# Power.net
KiCad netlist of a schematic drawn in Altium Designer
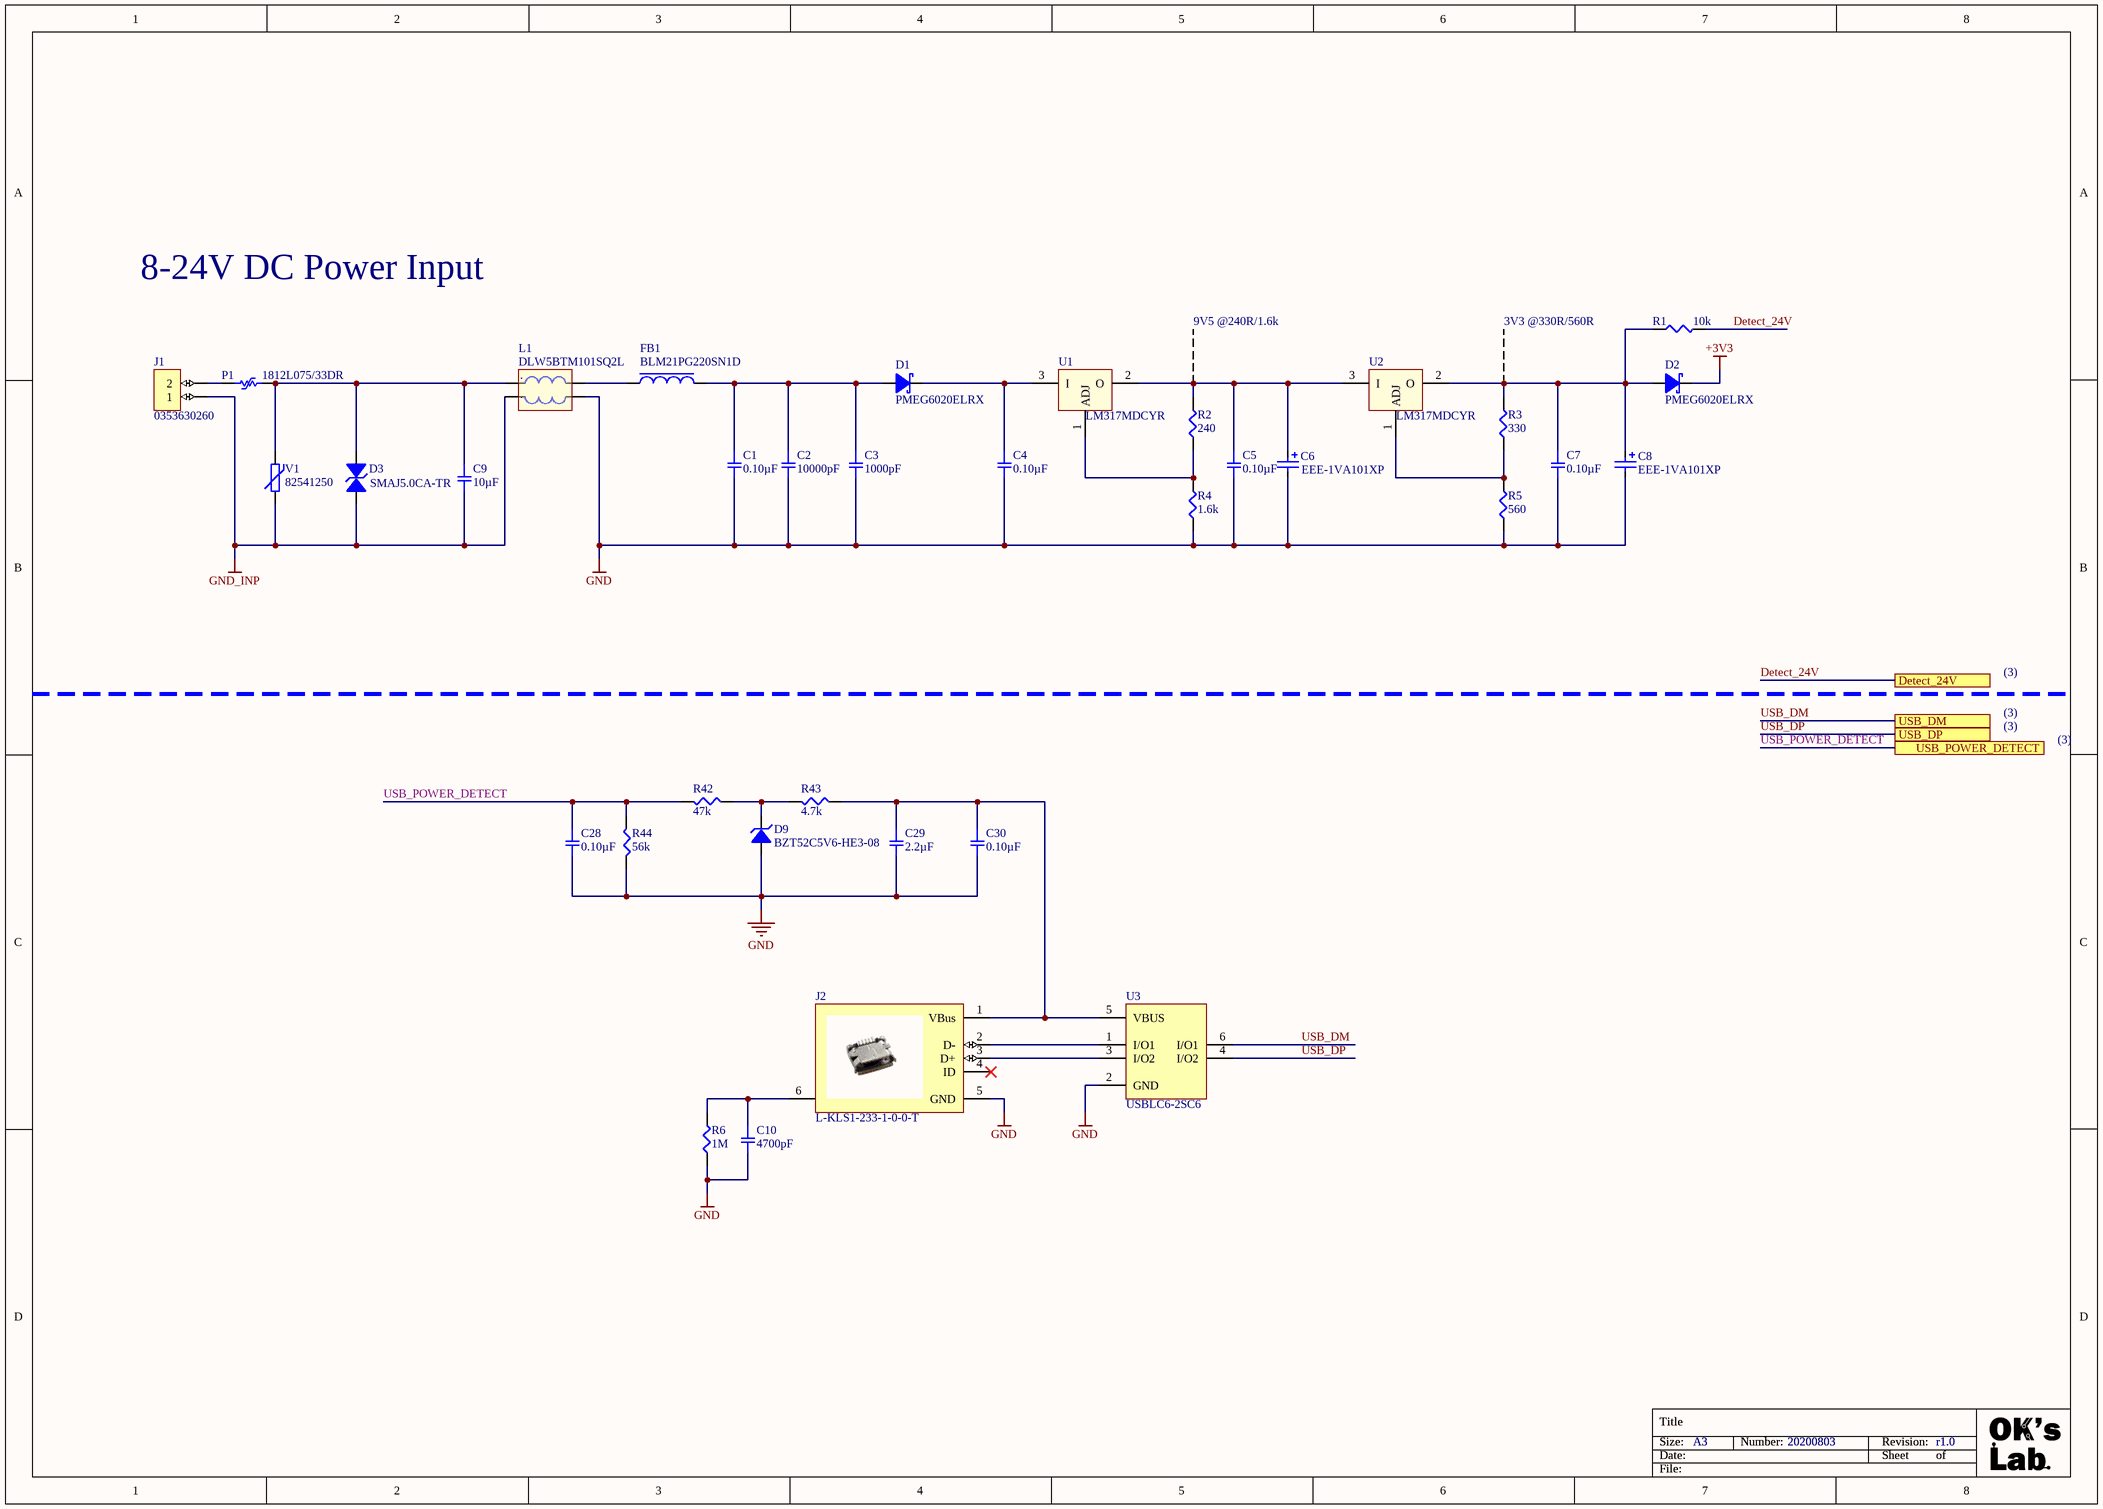
[diagram p0: Power.SchDoc]

(export (version "E")
  (design (tool "Eeschema 10.0.6"))
  (components
    (comp (ref "C1")
      (value "0.10µF")
      (footprint "SMD-0805C")
      (description "CAP CER 0.1UF 50V X7R 0805")
      (fields
        (field (name "DIGI-KEY PART NUMBER") "490-11955-1-ND")
        (field (name "PART NUMBER") "GCD21BR71H104KA01L")
      )
      (libsource (lib "capacitor_murata_0805") (part "GCD21BR71H104KA01L"))
    )
    (comp (ref "C2")
      (value "10000pF")
      (footprint "SMD-0805C")
      (description "CAP CER 10000PF 50V X7R 0805")
      (fields
        (field (name "DIGI-KEY PART NUMBER") "490-5841-1-ND")
        (field (name "PART NUMBER") "GCJ216R71H103KA01D")
      )
      (libsource (lib "capacitor_murata_0805") (part "GCJ216R71H103KA01D"))
    )
    (comp (ref "C3")
      (value "1000pF")
      (footprint "SMD-0805C")
      (description "CAP CER 1000PF 50V X7R 0805")
      (fields
        (field (name "DIGI-KEY PART NUMBER") "490-5813-1-ND")
        (field (name "PART NUMBER") "GCJ216R71H102KA01D")
      )
      (libsource (lib "capacitor_murata_0805") (part "GCJ216R71H102KA01D"))
    )
    (comp (ref "C4")
      (value "0.10µF")
      (footprint "SMD-0805C")
      (description "CAP CER 0.1UF 50V X7R 0805")
      (fields
        (field (name "DIGI-KEY PART NUMBER") "490-11955-1-ND")
        (field (name "PART NUMBER") "GCD21BR71H104KA01L")
      )
      (libsource (lib "capacitor_murata_0805") (part "GCD21BR71H104KA01L"))
    )
    (comp (ref "C5")
      (value "0.10µF")
      (footprint "SMD-0805C")
      (description "CAP CER 0.1UF 50V X7R 0805")
      (fields
        (field (name "DIGI-KEY PART NUMBER") "490-11955-1-ND")
        (field (name "PART NUMBER") "GCD21BR71H104KA01L")
      )
      (libsource (lib "capacitor_murata_0805") (part "GCD21BR71H104KA01L"))
    )
    (comp (ref "C6")
      (value "EEE-1VA101XP")
      (footprint "AE_C_R6")
      (description "CAP ALUM 100UF 20% 35V SMD")
      (fields
        (field (name "TOLERANCE") "±20%")
        (field (name "MANUFACTURER") "Panasonic Electronic Components")
      )
      (libsource (lib "Altium_Lib") (part "Capacitor_(Electrolytic)__EEE-1VA101XP"))
    )
    (comp (ref "C7")
      (value "0.10µF")
      (footprint "SMD-0805C")
      (description "CAP CER 0.1UF 50V X7R 0805")
      (fields
        (field (name "DIGI-KEY PART NUMBER") "490-11955-1-ND")
        (field (name "PART NUMBER") "GCD21BR71H104KA01L")
      )
      (libsource (lib "capacitor_murata_0805") (part "GCD21BR71H104KA01L"))
    )
    (comp (ref "C8")
      (value "EEE-1VA101XP")
      (footprint "AE_C_R6")
      (description "CAP ALUM 100UF 20% 35V SMD")
      (fields
        (field (name "TOLERANCE") "±20%")
        (field (name "MANUFACTURER") "Panasonic Electronic Components")
      )
      (libsource (lib "Altium_Lib") (part "Capacitor_(Electrolytic)__EEE-1VA101XP"))
    )
    (comp (ref "C9")
      (value "10µF")
      (footprint "SMD-1206C")
      (description "CAP CER 10UF 50V X5R 1206")
      (fields
        (field (name "DIGI-KEY PART NUMBER") "490-5961-1-ND")
        (field (name "PART NUMBER") "GRM31CR61H106KA12L")
      )
      (libsource (lib "capacitor_murata_1206") (part "GRM31CR61H106KA12L"))
    )
    (comp (ref "C10")
      (value "4700pF")
      (footprint "SMD-0805C")
      (description "CAP CER 4700PF 250V X7R 0805")
      (fields
        (field (name "DIGI-KEY PART NUMBER") "490-5593-1-ND")
        (field (name "PART NUMBER") "GCJ21AR72E472KXJ1D")
      )
      (libsource (lib "capacitor_murata_0805") (part "GCJ21AR72E472KXJ1D"))
    )
    (comp (ref "C28")
      (value "0.10µF")
      (footprint "SMD-0603C")
      (description "CAP CER 0.1UF 50V X7R 0603")
      (fields
        (field (name "DIGI-KEY PART NUMBER") "490-5798-1-ND")
        (field (name "MANUFACTURER") "Murata Electronics North America")
      )
      (libsource (lib "capacitor_murata_0603") (part "GCJ188R71H104KA12D"))
    )
    (comp (ref "C29")
      (value "2.2µF")
      (footprint "SMD-0603C")
      (description "CAP CER 2.2UF 16V X7S 0603")
      (fields
        (field (name "DIGI-KEY PART NUMBER") "490-12731-1-ND")
        (field (name "MANUFACTURER") "Murata Electronics North America")
      )
      (libsource (lib "capacitor_murata_0603") (part "GRM188C71C225KE11D"))
    )
    (comp (ref "C30")
      (value "0.10µF")
      (footprint "SMD-0603C")
      (description "CAP CER 0.1UF 50V X7R 0603")
      (fields
        (field (name "DIGI-KEY PART NUMBER") "490-5798-1-ND")
        (field (name "MANUFACTURER") "Murata Electronics North America")
      )
      (libsource (lib "capacitor_murata_0603") (part "GCJ188R71H104KA12D"))
    )
    (comp (ref "D1")
      (value "PMEG6020ELRX")
      (footprint "SOD123W")
      (description "DIODE SCHOTTKY 60V 2A CFP3")
      (fields (field (name "MANUFACTURER") "Nexperia"))
      (libsource (lib "Altium_Lib") (part "DIODE_PMEG6020ELRX"))
    )
    (comp (ref "D2")
      (value "PMEG6020ELRX")
      (footprint "SOD123W")
      (description "DIODE SCHOTTKY 60V 2A CFP3")
      (fields (field (name "MANUFACTURER") "Nexperia"))
      (libsource (lib "Altium_Lib") (part "DIODE_PMEG6020ELRX"))
    )
    (comp (ref "D3")
      (value "SMAJ5.0CA-TR")
      (footprint "DO-214AA-SMB -nonPOL")
      (description "TVS DIODE 26VWM 42.1VC SMB")
      (fields (field (name "MANUFACTURER") "STMicroelectronics") (field (name "BASE PART NUMBER") "SMAJ"))
      (libsource (lib "Altium_Lib") (part "DIODE_SMBJ26CA"))
    )
    (comp (ref "D9")
      (value "BZT52C5V6-HE3-08")
      (footprint "SOD123")
      (description "DIODE ZENER 5.6V 410MW SOD123")
      (fields (field (name "MANUFACTURER") "Vishay") (field (name "TOLERANCE") "5%"))
      (libsource (lib "Altium_Lib") (part "DIODE_BZT52C5V6-HE3-08"))
    )
    (comp (ref "FB1")
      (value "BLM21PG220SN1D")
      (footprint "L-0805")
      (description "FERRITE BEAD 22 OHM 0805 1LN")
      (fields (field (name "MANUFACTURER") "Murata") (field (name "TOLERANCE") "25%"))
      (libsource (lib "Altium_Lib") (part "Ferrite_Bead__BLM21PG220SN1D"))
    )
    (comp (ref "J1")
      (value "0353630260")
      (footprint "CONN_2_POS__0353630260")
      (description "CONN HEADER 2POS 2MM R/A TIN")
      (fields (field (name "MANUFACTURER") "Molex, LLC"))
      (libsource (lib "Altium_Lib") (part "CONN_2_POS__0353630260"))
    )
    (comp (ref "J2")
      (value "L-KLS1-233-1-0-0-T")
      (footprint "USB_MICRO_1981584-1")
      (description "Conn Micro USB 2.0 Type AB RCP 5 POS 0.65mm Solder RA SMD 5 Terminal 1 Port T/R")
      (fields (field (name "MANUFACTURER") "KLS Electronic"))
      (libsource (lib "Altium_Lib") (part "USB_Micro_L-KLS1-233-1-0-0-T"))
    )
    (comp (ref "L1")
      (value "DLW5BTM101SQ2L")
      (footprint "DLW5BTMxxxxxxx")
      (description "2 Line CommonModeChoke, SMD 6A")
      (libsource (lib "SinapstekLib") (part "DLW5BTM101SQ2L"))
    )
    (comp (ref "P1")
      (value "1812L075/33DR")
      (footprint "PTC-1812")
      (description "PTC RESET FUSE 33V 750MA 1812")
      (fields (field (name "MANUFACTURER") "Littelfuse Inc."))
      (libsource (lib "Altium_Lib") (part "PTC__1812L075/33DR"))
    )
    (comp (ref "R1")
      (value "10k")
      (footprint "SMD-0603-RES")
      (description "RES SMD 10K OHM 5% 1/10W 0603")
      (fields (field (name "PART NUMBER") "ERJ-3GEYJ103V") (field (name "DIGI-KEY PART NUMBER") "P10KGCT-ND"))
      (libsource (lib "Panasonic_ERJ_0603") (part "ERJ-3GEYJ103V"))
    )
    (comp (ref "R2")
      (value "240")
      (footprint "SMD-0603-RES")
      (description "RES SMD 240 OHM 1% 1/10W 0603")
      (fields (field (name "PART NUMBER") "ERJ-3EKF2400V") (field (name "DIGI-KEY PART NUMBER") "P240HCT-ND"))
      (libsource (lib "Panasonic_ERJ_0603") (part "ERJ-3EKF2400V"))
    )
    (comp (ref "R3")
      (value "330")
      (footprint "SMD-0603-RES")
      (description "RES SMD 330 OHM 1% 1/10W 0603")
      (fields (field (name "PART NUMBER") "ERJ-3EKF3300V") (field (name "DIGI-KEY PART NUMBER") "P330HCT-ND"))
      (libsource (lib "Panasonic_ERJ_0603") (part "ERJ-3EKF3300V"))
    )
    (comp (ref "R4")
      (value "1.6k")
      (footprint "SMD-0603-RES")
      (description "RES SMD 1.6K OHM 1% 1/10W 0603")
      (fields
        (field (name "PART NUMBER") "ERJ-3EKF1601V")
        (field (name "DIGI-KEY PART NUMBER") "P1.60KHCT-ND")
      )
      (libsource (lib "Panasonic_ERJ_0603") (part "ERJ-3EKF1601V"))
    )
    (comp (ref "R5")
      (value "560")
      (footprint "SMD-0603-RES")
      (description "RES SMD 560 OHM 1% 1/10W 0603")
      (fields (field (name "PART NUMBER") "ERJ-3EKF5600V") (field (name "DIGI-KEY PART NUMBER") "P560HCT-ND"))
      (libsource (lib "Panasonic_ERJ_0603") (part "ERJ-3EKF5600V"))
    )
    (comp (ref "R6")
      (value "1M")
      (footprint "SMD-0805-RES")
      (description "RES SMD 1M OHM 5% 1/8W 0805")
      (fields
        (field (name "PART NUMBER") "ERJ-6GEYJ105V")
        (field (name "DIGI-KEY PART NUMBER") "P1.0MACT-ND")
      )
      (libsource (lib "Panasonic_ERJ_0805") (part "ERJ-6GEYJ105V"))
    )
    (comp (ref "R42")
      (value "47k")
      (footprint "SMD-0603-RES")
      (description "RES SMD 47K OHM 1% 1/10W 0603")
      (fields
        (field (name "DIGI-KEY PART NUMBER") "P47.0KHCT-ND")
        (field (name "MANUFACTURER") "Panasonic Electronic Components")
      )
      (libsource (lib "Panasonic_ERJ_0603") (part "ERJ-3EKF4702V"))
    )
    (comp (ref "R43")
      (value "4.7k")
      (footprint "SMD-0603-RES")
      (description "RES SMD 4.7K OHM 1% 1/10W 0603")
      (fields
        (field (name "DIGI-KEY PART NUMBER") "P4.70KHCT-ND")
        (field (name "MANUFACTURER") "Panasonic Electronic Components")
      )
      (libsource (lib "Panasonic_ERJ_0603") (part "ERJ-3EKF4701V"))
    )
    (comp (ref "R44")
      (value "56k")
      (footprint "SMD-0603-RES")
      (description "RES SMD 56K OHM 1% 1/10W 0603")
      (fields
        (field (name "DIGI-KEY PART NUMBER") "P56.0KHCT-ND")
        (field (name "MANUFACTURER") "Panasonic Electronic Components")
      )
      (libsource (lib "Panasonic_ERJ_0603") (part "ERJ-3EKF5602V"))
    )
    (comp (ref "U1")
      (value "LM317MDCYR")
      (footprint "SOT-223-4")
      (description "IC REG LINEAR ADJ 0.5A SOT223")
      (fields (field (name "MANUFACTURER") "Texas Instruments"))
      (libsource (lib "Altium_Lib") (part "LM317MDCY"))
    )
    (comp (ref "U2")
      (value "LM317MDCYR")
      (footprint "SOT-223-4")
      (description "IC REG LINEAR ADJ 0.5A SOT223")
      (fields (field (name "MANUFACTURER") "Texas Instruments"))
      (libsource (lib "Altium_Lib") (part "LM317MDCY"))
    )
    (comp (ref "U3")
      (value "USBLC6-2SC6")
      (footprint "SOT23-6")
      (description "TVS DIODE 5.25V 17V SOT23-6")
      (fields (field (name "MANUFACTURER") "STMicroelectronics") (field (name "BASE PART NUMBER") "USBLC6-2"))
      (libsource (lib "Altium_Lib") (part "USBLC6-2SC6"))
    )
    (comp (ref "V1")
      (value "82541250")
      (footprint "V-1206")
      (description "VARISTOR 39V 200A 1206")
      (fields (field (name "MANUFACTURER") "Wurth Electronics Inc."))
      (libsource (lib "Altium_Lib") (part "VARISTOR_82541250"))
    )
  )
  (nets
    (net (code "1") (name "+3V3") (class "Default")
      (node (ref "D2") (pin "1") (pinfunction "K_1") (pintype "passive"))
    )
    (net (code "2") (name "/Detect_24V") (class "Default")
      (node (ref "R1") (pin "2") (pinfunction "2_2") (pintype "passive"))
    )
    (net (code "3") (name "/USB_DM") (class "Default")
      (node (ref "U3") (pin "6") (pinfunction "I/O1_6") (pintype "passive"))
    )
    (net (code "4") (name "/USB_DP") (class "Default")
      (node (ref "U3") (pin "4") (pinfunction "I/O2_4") (pintype "passive"))
    )
    (net (code "5") (name "/USB_POWER_DETECT") (class "Default")
      (node (ref "C28") (pin "1") (pinfunction "1_1") (pintype "passive"))
      (node (ref "R42") (pin "2") (pinfunction "2_2") (pintype "passive"))
      (node (ref "R44") (pin "2") (pinfunction "2_2") (pintype "passive"))
    )
    (net (code "6") (name "GND") (class "Default")
      (node (ref "C1") (pin "2") (pinfunction "2_2") (pintype "passive"))
      (node (ref "C10") (pin "2") (pinfunction "2_2") (pintype "passive"))
      (node (ref "C2") (pin "2") (pinfunction "2_2") (pintype "passive"))
      (node (ref "C28") (pin "2") (pinfunction "2_2") (pintype "passive"))
      (node (ref "C29") (pin "2") (pinfunction "2_2") (pintype "passive"))
      (node (ref "C3") (pin "2") (pinfunction "2_2") (pintype "passive"))
      (node (ref "C30") (pin "2") (pinfunction "2_2") (pintype "passive"))
      (node (ref "C4") (pin "2") (pinfunction "2_2") (pintype "passive"))
      (node (ref "C5") (pin "2") (pinfunction "2_2") (pintype "passive"))
      (node (ref "C6") (pin "2") (pinfunction "2_2") (pintype "passive"))
      (node (ref "C7") (pin "2") (pinfunction "2_2") (pintype "passive"))
      (node (ref "C8") (pin "2") (pinfunction "2_2") (pintype "passive"))
      (node (ref "D9") (pin "1") (pinfunction "T1_1") (pintype "passive"))
      (node (ref "J2") (pin "5") (pinfunction "GND_5") (pintype "passive"))
      (node (ref "L1") (pin "3") (pinfunction "B2_3") (pintype "passive"))
      (node (ref "R4") (pin "1") (pinfunction "1_1") (pintype "passive"))
      (node (ref "R44") (pin "1") (pinfunction "1_1") (pintype "passive"))
      (node (ref "R5") (pin "1") (pinfunction "1_1") (pintype "passive"))
      (node (ref "R6") (pin "1") (pinfunction "1_1") (pintype "passive"))
      (node (ref "U3") (pin "2") (pinfunction "GND_2") (pintype "passive"))
    )
    (net (code "7") (name "GND_INP") (class "Default")
      (node (ref "C9") (pin "2") (pinfunction "2_2") (pintype "passive"))
      (node (ref "D3") (pin "2") (pinfunction "T2_2") (pintype "passive"))
      (node (ref "J1") (pin "1") (pinfunction "1_1") (pintype "bidirectional"))
      (node (ref "L1") (pin "4") (pinfunction "B1_4") (pintype "passive"))
      (node (ref "V1") (pin "1") (pinfunction "1_1") (pintype "passive"))
    )
    (net (code "8") (name "Net-(D1-A)") (class "Default")
      (node (ref "C1") (pin "1") (pinfunction "1_1") (pintype "passive"))
      (node (ref "C2") (pin "1") (pinfunction "1_1") (pintype "passive"))
      (node (ref "C3") (pin "1") (pinfunction "1_1") (pintype "passive"))
      (node (ref "D1") (pin "2") (pinfunction "A_2") (pintype "passive"))
      (node (ref "FB1") (pin "2") (pinfunction "2_2") (pintype "passive"))
    )
    (net (code "9") (name "Net-(D1-K)") (class "Default")
      (node (ref "C4") (pin "1") (pinfunction "1_1") (pintype "passive"))
      (node (ref "D1") (pin "1") (pinfunction "K_1") (pintype "passive"))
      (node (ref "U1") (pin "3") (pinfunction "I_3") (pintype "power_in"))
    )
    (net (code "10") (name "Net-(D2-A)") (class "Default")
      (node (ref "C7") (pin "1") (pinfunction "1_1") (pintype "passive"))
      (node (ref "C8") (pin "1") (pinfunction "1_1") (pintype "passive"))
      (node (ref "D2") (pin "2") (pinfunction "A_2") (pintype "passive"))
      (node (ref "R1") (pin "1") (pinfunction "1_1") (pintype "passive"))
      (node (ref "R3") (pin "2") (pinfunction "2_2") (pintype "passive"))
      (node (ref "U2") (pin "2") (pinfunction "O_2") (pintype "power_in"))
    )
    (net (code "11") (name "Net-(D3-T1)") (class "Default")
      (node (ref "C9") (pin "1") (pinfunction "1_1") (pintype "passive"))
      (node (ref "D3") (pin "1") (pinfunction "T1_1") (pintype "passive"))
      (node (ref "L1") (pin "1") (pinfunction "A1_1") (pintype "passive"))
      (node (ref "P1") (pin "2") (pinfunction "2_2") (pintype "passive"))
      (node (ref "V1") (pin "2") (pinfunction "2_2") (pintype "passive"))
    )
    (net (code "12") (name "Net-(D9-T2)") (class "Default")
      (node (ref "D9") (pin "2") (pinfunction "T2_2") (pintype "passive"))
      (node (ref "R42") (pin "1") (pinfunction "1_1") (pintype "passive"))
      (node (ref "R43") (pin "2") (pinfunction "2_2") (pintype "passive"))
    )
    (net (code "13") (name "Net-(J1-Pad2)") (class "Default")
      (node (ref "J1") (pin "2") (pinfunction "2_2") (pintype "bidirectional"))
      (node (ref "P1") (pin "1") (pinfunction "1_1") (pintype "passive"))
    )
    (net (code "14") (name "Net-(J2-D+)") (class "Default")
      (node (ref "J2") (pin "3") (pinfunction "D+_3") (pintype "bidirectional"))
      (node (ref "U3") (pin "3") (pinfunction "I/O2_3") (pintype "passive"))
    )
    (net (code "15") (name "Net-(J2-D-)") (class "Default")
      (node (ref "J2") (pin "2") (pinfunction "D-_2") (pintype "bidirectional"))
      (node (ref "U3") (pin "1") (pinfunction "I/O1_1") (pintype "passive"))
    )
    (net (code "16") (name "Net-(J2-Shield)") (class "Default")
      (node (ref "C10") (pin "1") (pinfunction "1_1") (pintype "passive"))
      (node (ref "J2") (pin "6") (pinfunction "Shield_6") (pintype "passive"))
      (node (ref "R6") (pin "2") (pinfunction "2_2") (pintype "passive"))
    )
    (net (code "17") (name "Net-(J2-VBus)") (class "Default")
      (node (ref "C29") (pin "1") (pinfunction "1_1") (pintype "passive"))
      (node (ref "C30") (pin "1") (pinfunction "1_1") (pintype "passive"))
      (node (ref "J2") (pin "1") (pinfunction "VBus_1") (pintype "power_in"))
      (node (ref "R43") (pin "1") (pinfunction "1_1") (pintype "passive"))
      (node (ref "U3") (pin "5") (pinfunction "VBUS_5") (pintype "passive"))
    )
    (net (code "18") (name "Net-(L1-A2)") (class "Default")
      (node (ref "FB1") (pin "1") (pinfunction "1_1") (pintype "passive"))
      (node (ref "L1") (pin "2") (pinfunction "A2_2") (pintype "passive"))
    )
    (net (code "19") (name "Net-(U1-ADJ)") (class "Default")
      (node (ref "R2") (pin "1") (pinfunction "1_1") (pintype "passive"))
      (node (ref "R4") (pin "2") (pinfunction "2_2") (pintype "passive"))
      (node (ref "U1") (pin "1") (pinfunction "ADJ_1") (pintype "power_in"))
    )
    (net (code "20") (name "Net-(U1-O)") (class "Default")
      (node (ref "C5") (pin "1") (pinfunction "1_1") (pintype "passive"))
      (node (ref "C6") (pin "1") (pinfunction "1_1") (pintype "passive"))
      (node (ref "R2") (pin "2") (pinfunction "2_2") (pintype "passive"))
      (node (ref "U1") (pin "2") (pinfunction "O_2") (pintype "power_in"))
      (node (ref "U2") (pin "3") (pinfunction "I_3") (pintype "power_in"))
    )
    (net (code "21") (name "Net-(U2-ADJ)") (class "Default")
      (node (ref "R3") (pin "1") (pinfunction "1_1") (pintype "passive"))
      (node (ref "R5") (pin "2") (pinfunction "2_2") (pintype "passive"))
      (node (ref "U2") (pin "1") (pinfunction "ADJ_1") (pintype "power_in"))
    )
    (net (code "22") (name "unconnected-(J2-ID-Pad4)") (class "Default")
      (node (ref "J2") (pin "4") (pinfunction "ID_4") (pintype "power_in+no_connect"))
    )
  )
)
